# rev02_22.net
KiCad netlist of a schematic drawn in Altium Designer
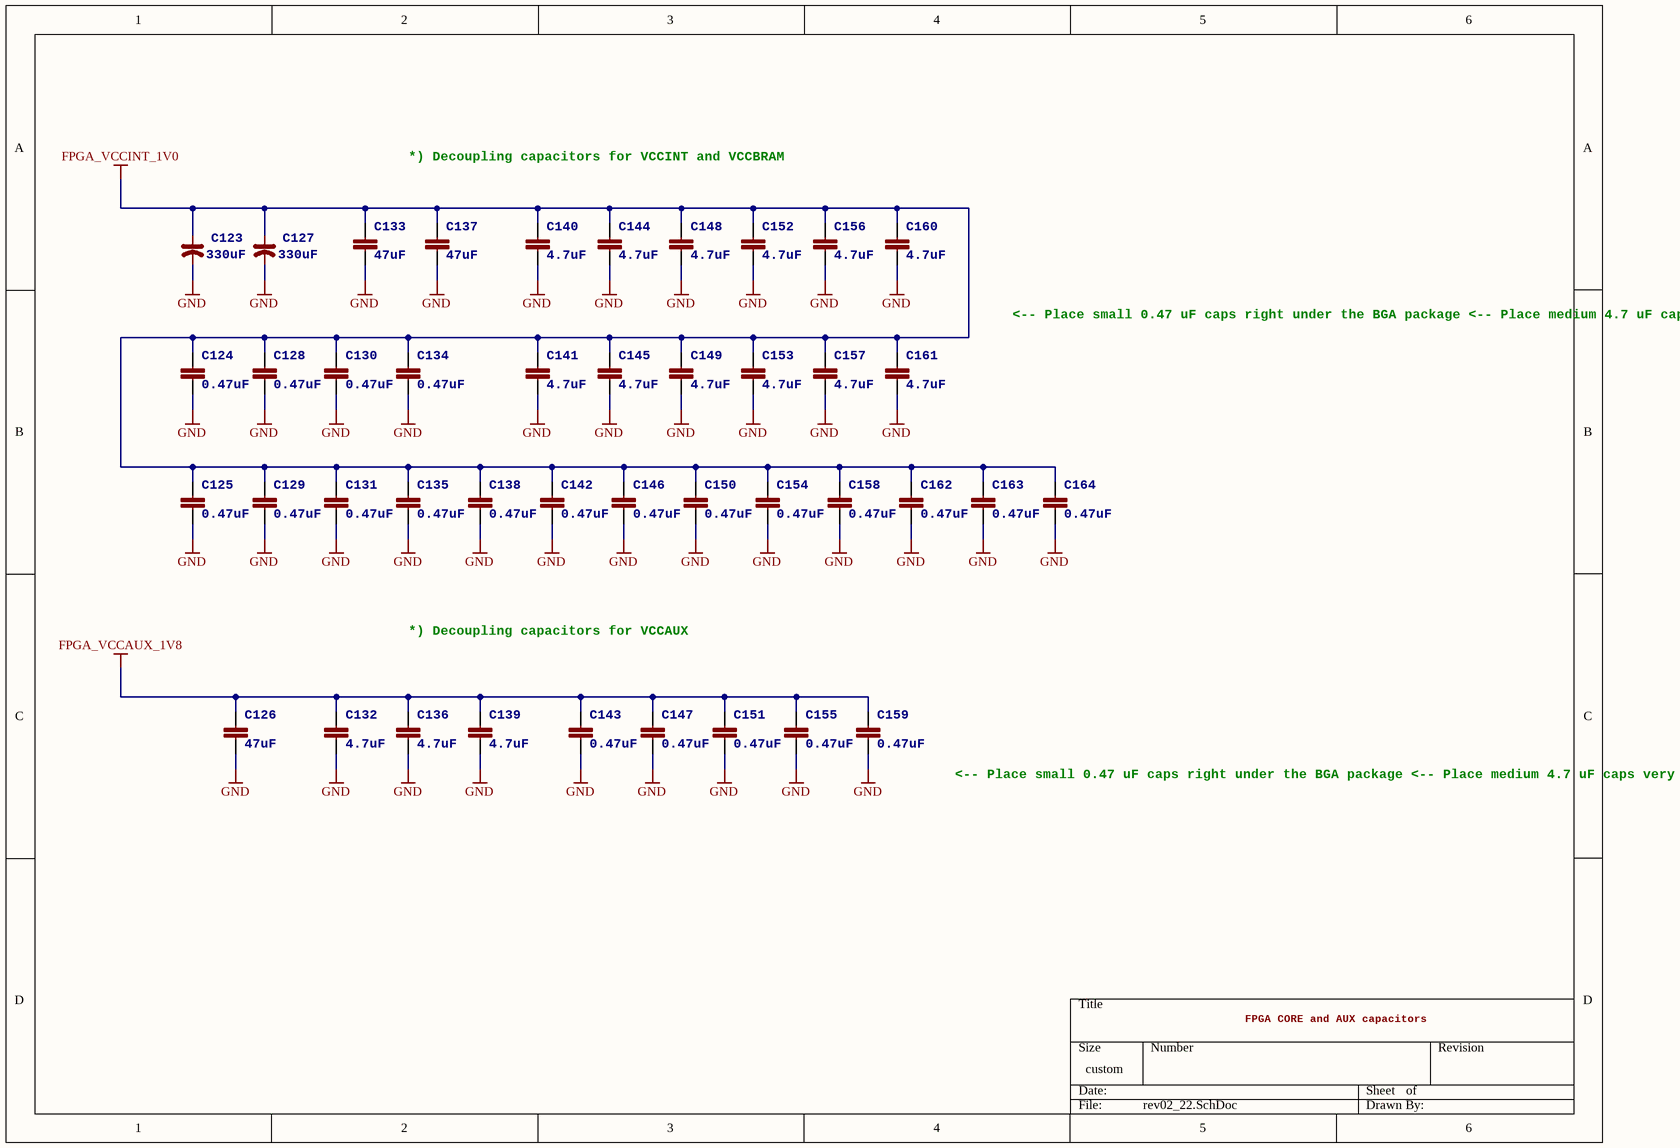
[diagram p0: rev02_22.SchDoc]

(export (version "E")
  (design (tool "Eeschema 10.0.6"))
  (components
    (comp (ref "C123")
      (value "330uF")
      (footprint "C_D")
      (description "Kemet Tantalum Capacitor")
      (fields (field (name "Comment") "T520D337M006ATE015"))
      (libsource (lib "rev02_1") (part "CP_E-035X080"))
    )
    (comp (ref "C124")
      (value "0.47uF")
      (footprint "C_0402")
      (description "0402 CAPACITOR")
      (fields
        (field (name "TOLERANCE") "10%")
        (field (name ">NAME") "C124")
        (field (name "Comment") "GRM155R61A474KE15D")
      )
      (libsource (lib "resistor") (part "C-EUC0402"))
    )
    (comp (ref "C125")
      (value "0.47uF")
      (footprint "C_0402")
      (description "0402 CAPACITOR")
      (fields
        (field (name "TOLERANCE") "10%")
        (field (name ">NAME") "C125")
        (field (name "Comment") "GRM155R61A474KE15D")
      )
      (libsource (lib "resistor") (part "C-EUC0402"))
    )
    (comp (ref "C126")
      (value "47uF")
      (footprint "C_1210")
      (description "1210 CAPACITOR X5R 6.3V")
      (fields
        (field (name "TOLERANCE") "20%")
        (field (name ">NAME") "C126")
        (field (name "Comment") "GRM32ER70J476ME20L")
      )
      (libsource (lib "resistor") (part "C-EUC1210"))
    )
    (comp (ref "C127")
      (value "330uF")
      (footprint "C_D")
      (description "Kemet Tantalum Capacitor")
      (fields (field (name "Comment") "T520D337M006ATE015"))
      (libsource (lib "rev02_1") (part "CP_E-035X080"))
    )
    (comp (ref "C128")
      (value "0.47uF")
      (footprint "C_0402")
      (description "0402 CAPACITOR")
      (fields
        (field (name "TOLERANCE") "10%")
        (field (name ">NAME") "C128")
        (field (name "Comment") "GRM155R61A474KE15D")
      )
      (libsource (lib "resistor") (part "C-EUC0402"))
    )
    (comp (ref "C129")
      (value "0.47uF")
      (footprint "C_0402")
      (description "0402 CAPACITOR")
      (fields
        (field (name "TOLERANCE") "10%")
        (field (name ">NAME") "C129")
        (field (name "Comment") "GRM155R61A474KE15D")
      )
      (libsource (lib "resistor") (part "C-EUC0402"))
    )
    (comp (ref "C130")
      (value "0.47uF")
      (footprint "C_0402")
      (description "0402 CAPACITOR")
      (fields
        (field (name "TOLERANCE") "10%")
        (field (name ">NAME") "C130")
        (field (name "Comment") "GRM155R61A474KE15D")
      )
      (libsource (lib "resistor") (part "C-EUC0402"))
    )
    (comp (ref "C131")
      (value "0.47uF")
      (footprint "C_0402")
      (description "0402 CAPACITOR")
      (fields
        (field (name "TOLERANCE") "10%")
        (field (name ">NAME") "C131")
        (field (name "Comment") "GRM155R61A474KE15D")
      )
      (libsource (lib "resistor") (part "C-EUC0402"))
    )
    (comp (ref "C132")
      (value "4.7uF")
      (footprint "C_0805")
      (description "0805 CAPACITOR")
      (fields
        (field (name "TOLERANCE") "10%")
        (field (name ">NAME") "C132")
        (field (name "Comment") "GRM21BR71A475KA73L")
      )
      (libsource (lib "resistor") (part "C-EUC0603"))
    )
    (comp (ref "C133")
      (value "47uF")
      (footprint "C_1210")
      (description "1210 CAPACITOR X5R 6.3V")
      (fields
        (field (name "TOLERANCE") "20%")
        (field (name ">NAME") "C133")
        (field (name "Comment") "GRM32ER70J476ME20L")
      )
      (libsource (lib "resistor") (part "C-EUC1210"))
    )
    (comp (ref "C134")
      (value "0.47uF")
      (footprint "C_0402")
      (description "0402 CAPACITOR")
      (fields
        (field (name "TOLERANCE") "10%")
        (field (name ">NAME") "C134")
        (field (name "Comment") "GRM155R61A474KE15D")
      )
      (libsource (lib "resistor") (part "C-EUC0402"))
    )
    (comp (ref "C135")
      (value "0.47uF")
      (footprint "C_0402")
      (description "0402 CAPACITOR")
      (fields
        (field (name "TOLERANCE") "10%")
        (field (name ">NAME") "C135")
        (field (name "Comment") "GRM155R61A474KE15D")
      )
      (libsource (lib "resistor") (part "C-EUC0402"))
    )
    (comp (ref "C136")
      (value "4.7uF")
      (footprint "C_0805")
      (description "0805 CAPACITOR")
      (fields
        (field (name "TOLERANCE") "10%")
        (field (name ">NAME") "C136")
        (field (name "Comment") "GRM21BR71A475KA73L")
      )
      (libsource (lib "resistor") (part "C-EUC0603"))
    )
    (comp (ref "C137")
      (value "47uF")
      (footprint "C_1210")
      (description "1210 CAPACITOR X5R 6.3V")
      (fields
        (field (name "TOLERANCE") "20%")
        (field (name ">NAME") "C137")
        (field (name "Comment") "GRM32ER70J476ME20L")
      )
      (libsource (lib "resistor") (part "C-EUC1210"))
    )
    (comp (ref "C138")
      (value "0.47uF")
      (footprint "C_0402")
      (description "0402 CAPACITOR")
      (fields
        (field (name "TOLERANCE") "10%")
        (field (name ">NAME") "C138")
        (field (name "Comment") "GRM155R61A474KE15D")
      )
      (libsource (lib "resistor") (part "C-EUC0402"))
    )
    (comp (ref "C139")
      (value "4.7uF")
      (footprint "C_0805")
      (description "0805 CAPACITOR")
      (fields
        (field (name "TOLERANCE") "10%")
        (field (name ">NAME") "C139")
        (field (name "Comment") "GRM21BR71A475KA73L")
      )
      (libsource (lib "resistor") (part "C-EUC0603"))
    )
    (comp (ref "C140")
      (value "4.7uF")
      (footprint "C_0805")
      (description "0805 CAPACITOR")
      (fields
        (field (name "TOLERANCE") "10%")
        (field (name ">NAME") "C140")
        (field (name "Comment") "GRM21BR71A475KA73L")
      )
      (libsource (lib "resistor") (part "C-EUC0603"))
    )
    (comp (ref "C141")
      (value "4.7uF")
      (footprint "C_0805")
      (description "0805 CAPACITOR")
      (fields
        (field (name "TOLERANCE") "10%")
        (field (name ">NAME") "C141")
        (field (name "Comment") "GRM21BR71A475KA73L")
      )
      (libsource (lib "resistor") (part "C-EUC0603"))
    )
    (comp (ref "C142")
      (value "0.47uF")
      (footprint "C_0402")
      (description "0402 CAPACITOR")
      (fields
        (field (name "TOLERANCE") "10%")
        (field (name ">NAME") "C142")
        (field (name "Comment") "GRM155R61A474KE15D")
      )
      (libsource (lib "resistor") (part "C-EUC0402"))
    )
    (comp (ref "C143")
      (value "0.47uF")
      (footprint "C_0402")
      (description "0402 CAPACITOR")
      (fields
        (field (name "TOLERANCE") "10%")
        (field (name ">NAME") "C143")
        (field (name "Comment") "GRM155R61A474KE15D")
      )
      (libsource (lib "resistor") (part "C-EUC0402"))
    )
    (comp (ref "C144")
      (value "4.7uF")
      (footprint "C_0805")
      (description "0805 CAPACITOR")
      (fields
        (field (name "TOLERANCE") "10%")
        (field (name ">NAME") "C144")
        (field (name "Comment") "GRM21BR71A475KA73L")
      )
      (libsource (lib "resistor") (part "C-EUC0603"))
    )
    (comp (ref "C145")
      (value "4.7uF")
      (footprint "C_0805")
      (description "0805 CAPACITOR")
      (fields
        (field (name "TOLERANCE") "10%")
        (field (name ">NAME") "C145")
        (field (name "Comment") "GRM21BR71A475KA73L")
      )
      (libsource (lib "resistor") (part "C-EUC0603"))
    )
    (comp (ref "C146")
      (value "0.47uF")
      (footprint "C_0402")
      (description "0402 CAPACITOR")
      (fields
        (field (name "TOLERANCE") "10%")
        (field (name ">NAME") "C146")
        (field (name "Comment") "GRM155R61A474KE15D")
      )
      (libsource (lib "resistor") (part "C-EUC0402"))
    )
    (comp (ref "C147")
      (value "0.47uF")
      (footprint "C_0402")
      (description "0402 CAPACITOR")
      (fields
        (field (name "TOLERANCE") "10%")
        (field (name ">NAME") "C147")
        (field (name "Comment") "GRM155R61A474KE15D")
      )
      (libsource (lib "resistor") (part "C-EUC0402"))
    )
    (comp (ref "C148")
      (value "4.7uF")
      (footprint "C_0805")
      (description "0805 CAPACITOR")
      (fields
        (field (name "TOLERANCE") "10%")
        (field (name ">NAME") "C148")
        (field (name "Comment") "GRM21BR71A475KA73L")
      )
      (libsource (lib "resistor") (part "C-EUC0603"))
    )
    (comp (ref "C149")
      (value "4.7uF")
      (footprint "C_0805")
      (description "0805 CAPACITOR")
      (fields
        (field (name "TOLERANCE") "10%")
        (field (name ">NAME") "C149")
        (field (name "Comment") "GRM21BR71A475KA73L")
      )
      (libsource (lib "resistor") (part "C-EUC0603"))
    )
    (comp (ref "C150")
      (value "0.47uF")
      (footprint "C_0402")
      (description "0402 CAPACITOR")
      (fields
        (field (name "TOLERANCE") "10%")
        (field (name ">NAME") "C150")
        (field (name "Comment") "GRM155R61A474KE15D")
      )
      (libsource (lib "resistor") (part "C-EUC0402"))
    )
    (comp (ref "C151")
      (value "0.47uF")
      (footprint "C_0402")
      (description "0402 CAPACITOR")
      (fields
        (field (name "TOLERANCE") "10%")
        (field (name ">NAME") "C151")
        (field (name "Comment") "GRM155R61A474KE15D")
      )
      (libsource (lib "resistor") (part "C-EUC0402"))
    )
    (comp (ref "C152")
      (value "4.7uF")
      (footprint "C_0805")
      (description "0805 CAPACITOR")
      (fields
        (field (name "TOLERANCE") "10%")
        (field (name ">NAME") "C152")
        (field (name "Comment") "GRM21BR71A475KA73L")
      )
      (libsource (lib "resistor") (part "C-EUC0603"))
    )
    (comp (ref "C153")
      (value "4.7uF")
      (footprint "C_0805")
      (description "0805 CAPACITOR")
      (fields
        (field (name "TOLERANCE") "10%")
        (field (name ">NAME") "C153")
        (field (name "Comment") "GRM21BR71A475KA73L")
      )
      (libsource (lib "resistor") (part "C-EUC0603"))
    )
    (comp (ref "C154")
      (value "0.47uF")
      (footprint "C_0402")
      (description "0402 CAPACITOR")
      (fields
        (field (name "TOLERANCE") "10%")
        (field (name ">NAME") "C154")
        (field (name "Comment") "GRM155R61A474KE15D")
      )
      (libsource (lib "resistor") (part "C-EUC0402"))
    )
    (comp (ref "C155")
      (value "0.47uF")
      (footprint "C_0402")
      (description "0402 CAPACITOR")
      (fields
        (field (name "TOLERANCE") "10%")
        (field (name ">NAME") "C155")
        (field (name "Comment") "GRM155R61A474KE15D")
      )
      (libsource (lib "resistor") (part "C-EUC0402"))
    )
    (comp (ref "C156")
      (value "4.7uF")
      (footprint "C_0805")
      (description "0805 CAPACITOR")
      (fields
        (field (name "TOLERANCE") "10%")
        (field (name ">NAME") "C156")
        (field (name "Comment") "GRM21BR71A475KA73L")
      )
      (libsource (lib "resistor") (part "C-EUC0603"))
    )
    (comp (ref "C157")
      (value "4.7uF")
      (footprint "C_0805")
      (description "0805 CAPACITOR")
      (fields
        (field (name "TOLERANCE") "10%")
        (field (name ">NAME") "C157")
        (field (name "Comment") "GRM21BR71A475KA73L")
      )
      (libsource (lib "resistor") (part "C-EUC0603"))
    )
    (comp (ref "C158")
      (value "0.47uF")
      (footprint "C_0402")
      (description "0402 CAPACITOR")
      (fields
        (field (name "TOLERANCE") "10%")
        (field (name ">NAME") "C158")
        (field (name "Comment") "GRM155R61A474KE15D")
      )
      (libsource (lib "resistor") (part "C-EUC0402"))
    )
    (comp (ref "C159")
      (value "0.47uF")
      (footprint "C_0402")
      (description "0402 CAPACITOR")
      (fields
        (field (name "TOLERANCE") "10%")
        (field (name ">NAME") "C159")
        (field (name "Comment") "GRM155R61A474KE15D")
      )
      (libsource (lib "resistor") (part "C-EUC0402"))
    )
    (comp (ref "C160")
      (value "4.7uF")
      (footprint "C_0805")
      (description "0805 CAPACITOR")
      (fields
        (field (name "TOLERANCE") "10%")
        (field (name ">NAME") "C160")
        (field (name "Comment") "GRM21BR71A475KA73L")
      )
      (libsource (lib "resistor") (part "C-EUC0603"))
    )
    (comp (ref "C161")
      (value "4.7uF")
      (footprint "C_0805")
      (description "0805 CAPACITOR")
      (fields
        (field (name "TOLERANCE") "10%")
        (field (name ">NAME") "C161")
        (field (name "Comment") "GRM21BR71A475KA73L")
      )
      (libsource (lib "resistor") (part "C-EUC0603"))
    )
    (comp (ref "C162")
      (value "0.47uF")
      (footprint "C_0402")
      (description "0402 CAPACITOR")
      (fields
        (field (name "TOLERANCE") "10%")
        (field (name ">NAME") "C162")
        (field (name "Comment") "GRM155R61A474KE15D")
      )
      (libsource (lib "resistor") (part "C-EUC0402"))
    )
    (comp (ref "C163")
      (value "0.47uF")
      (footprint "C_0402")
      (description "0402 CAPACITOR")
      (fields
        (field (name "TOLERANCE") "10%")
        (field (name ">NAME") "C163")
        (field (name "Comment") "GRM155R61A474KE15D")
      )
      (libsource (lib "resistor") (part "C-EUC0402"))
    )
    (comp (ref "C164")
      (value "0.47uF")
      (footprint "C_0402")
      (description "0402 CAPACITOR")
      (fields
        (field (name "TOLERANCE") "10%")
        (field (name ">NAME") "C164")
        (field (name "Comment") "GRM155R61A474KE15D")
      )
      (libsource (lib "resistor") (part "C-EUC0402"))
    )
  )
  (nets
    (net (code "1") (name "FPGA_VCCAUX_1V8") (class "Default")
      (node (ref "C126") (pin "1") (pinfunction "1_1") (pintype "passive"))
      (node (ref "C132") (pin "1") (pinfunction "1_1") (pintype "passive"))
      (node (ref "C136") (pin "1") (pinfunction "1_1") (pintype "passive"))
      (node (ref "C139") (pin "1") (pinfunction "1_1") (pintype "passive"))
      (node (ref "C143") (pin "1") (pinfunction "1_1") (pintype "passive"))
      (node (ref "C147") (pin "1") (pinfunction "1_1") (pintype "passive"))
      (node (ref "C151") (pin "1") (pinfunction "1_1") (pintype "passive"))
      (node (ref "C155") (pin "1") (pinfunction "1_1") (pintype "passive"))
      (node (ref "C159") (pin "1") (pinfunction "1_1") (pintype "passive"))
    )
    (net (code "2") (name "FPGA_VCCINT_1V0") (class "Default")
      (node (ref "C123") (pin "1") (pinfunction "+_1") (pintype "passive"))
      (node (ref "C124") (pin "1") (pinfunction "1_1") (pintype "passive"))
      (node (ref "C125") (pin "1") (pinfunction "1_1") (pintype "passive"))
      (node (ref "C127") (pin "1") (pinfunction "+_1") (pintype "passive"))
      (node (ref "C128") (pin "1") (pinfunction "1_1") (pintype "passive"))
      (node (ref "C129") (pin "1") (pinfunction "1_1") (pintype "passive"))
      (node (ref "C130") (pin "1") (pinfunction "1_1") (pintype "passive"))
      (node (ref "C131") (pin "1") (pinfunction "1_1") (pintype "passive"))
      (node (ref "C133") (pin "1") (pinfunction "1_1") (pintype "passive"))
      (node (ref "C134") (pin "1") (pinfunction "1_1") (pintype "passive"))
      (node (ref "C135") (pin "1") (pinfunction "1_1") (pintype "passive"))
      (node (ref "C137") (pin "1") (pinfunction "1_1") (pintype "passive"))
      (node (ref "C138") (pin "1") (pinfunction "1_1") (pintype "passive"))
      (node (ref "C140") (pin "1") (pinfunction "1_1") (pintype "passive"))
      (node (ref "C141") (pin "1") (pinfunction "1_1") (pintype "passive"))
      (node (ref "C142") (pin "1") (pinfunction "1_1") (pintype "passive"))
      (node (ref "C144") (pin "1") (pinfunction "1_1") (pintype "passive"))
      (node (ref "C145") (pin "1") (pinfunction "1_1") (pintype "passive"))
      (node (ref "C146") (pin "1") (pinfunction "1_1") (pintype "passive"))
      (node (ref "C148") (pin "1") (pinfunction "1_1") (pintype "passive"))
      (node (ref "C149") (pin "1") (pinfunction "1_1") (pintype "passive"))
      (node (ref "C150") (pin "1") (pinfunction "1_1") (pintype "passive"))
      (node (ref "C152") (pin "1") (pinfunction "1_1") (pintype "passive"))
      (node (ref "C153") (pin "1") (pinfunction "1_1") (pintype "passive"))
      (node (ref "C154") (pin "1") (pinfunction "1_1") (pintype "passive"))
      (node (ref "C156") (pin "1") (pinfunction "1_1") (pintype "passive"))
      (node (ref "C157") (pin "1") (pinfunction "1_1") (pintype "passive"))
      (node (ref "C158") (pin "1") (pinfunction "1_1") (pintype "passive"))
      (node (ref "C160") (pin "1") (pinfunction "1_1") (pintype "passive"))
      (node (ref "C161") (pin "1") (pinfunction "1_1") (pintype "passive"))
      (node (ref "C162") (pin "1") (pinfunction "1_1") (pintype "passive"))
      (node (ref "C163") (pin "1") (pinfunction "1_1") (pintype "passive"))
      (node (ref "C164") (pin "1") (pinfunction "1_1") (pintype "passive"))
    )
    (net (code "3") (name "GND") (class "Default")
      (node (ref "C123") (pin "2") (pinfunction "-_2") (pintype "passive"))
      (node (ref "C124") (pin "2") (pinfunction "2_2") (pintype "passive"))
      (node (ref "C125") (pin "2") (pinfunction "2_2") (pintype "passive"))
      (node (ref "C126") (pin "2") (pinfunction "2_2") (pintype "passive"))
      (node (ref "C127") (pin "2") (pinfunction "-_2") (pintype "passive"))
      (node (ref "C128") (pin "2") (pinfunction "2_2") (pintype "passive"))
      (node (ref "C129") (pin "2") (pinfunction "2_2") (pintype "passive"))
      (node (ref "C130") (pin "2") (pinfunction "2_2") (pintype "passive"))
      (node (ref "C131") (pin "2") (pinfunction "2_2") (pintype "passive"))
      (node (ref "C132") (pin "2") (pinfunction "2_2") (pintype "passive"))
      (node (ref "C133") (pin "2") (pinfunction "2_2") (pintype "passive"))
      (node (ref "C134") (pin "2") (pinfunction "2_2") (pintype "passive"))
      (node (ref "C135") (pin "2") (pinfunction "2_2") (pintype "passive"))
      (node (ref "C136") (pin "2") (pinfunction "2_2") (pintype "passive"))
      (node (ref "C137") (pin "2") (pinfunction "2_2") (pintype "passive"))
      (node (ref "C138") (pin "2") (pinfunction "2_2") (pintype "passive"))
      (node (ref "C139") (pin "2") (pinfunction "2_2") (pintype "passive"))
      (node (ref "C140") (pin "2") (pinfunction "2_2") (pintype "passive"))
      (node (ref "C141") (pin "2") (pinfunction "2_2") (pintype "passive"))
      (node (ref "C142") (pin "2") (pinfunction "2_2") (pintype "passive"))
      (node (ref "C143") (pin "2") (pinfunction "2_2") (pintype "passive"))
      (node (ref "C144") (pin "2") (pinfunction "2_2") (pintype "passive"))
      (node (ref "C145") (pin "2") (pinfunction "2_2") (pintype "passive"))
      (node (ref "C146") (pin "2") (pinfunction "2_2") (pintype "passive"))
      (node (ref "C147") (pin "2") (pinfunction "2_2") (pintype "passive"))
      (node (ref "C148") (pin "2") (pinfunction "2_2") (pintype "passive"))
      (node (ref "C149") (pin "2") (pinfunction "2_2") (pintype "passive"))
      (node (ref "C150") (pin "2") (pinfunction "2_2") (pintype "passive"))
      (node (ref "C151") (pin "2") (pinfunction "2_2") (pintype "passive"))
      (node (ref "C152") (pin "2") (pinfunction "2_2") (pintype "passive"))
      (node (ref "C153") (pin "2") (pinfunction "2_2") (pintype "passive"))
      (node (ref "C154") (pin "2") (pinfunction "2_2") (pintype "passive"))
      (node (ref "C155") (pin "2") (pinfunction "2_2") (pintype "passive"))
      (node (ref "C156") (pin "2") (pinfunction "2_2") (pintype "passive"))
      (node (ref "C157") (pin "2") (pinfunction "2_2") (pintype "passive"))
      (node (ref "C158") (pin "2") (pinfunction "2_2") (pintype "passive"))
      (node (ref "C159") (pin "2") (pinfunction "2_2") (pintype "passive"))
      (node (ref "C160") (pin "2") (pinfunction "2_2") (pintype "passive"))
      (node (ref "C161") (pin "2") (pinfunction "2_2") (pintype "passive"))
      (node (ref "C162") (pin "2") (pinfunction "2_2") (pintype "passive"))
      (node (ref "C163") (pin "2") (pinfunction "2_2") (pintype "passive"))
      (node (ref "C164") (pin "2") (pinfunction "2_2") (pintype "passive"))
    )
  )
)
